# cell_fuses.net
KiCad netlist of a schematic drawn in Altium Designer
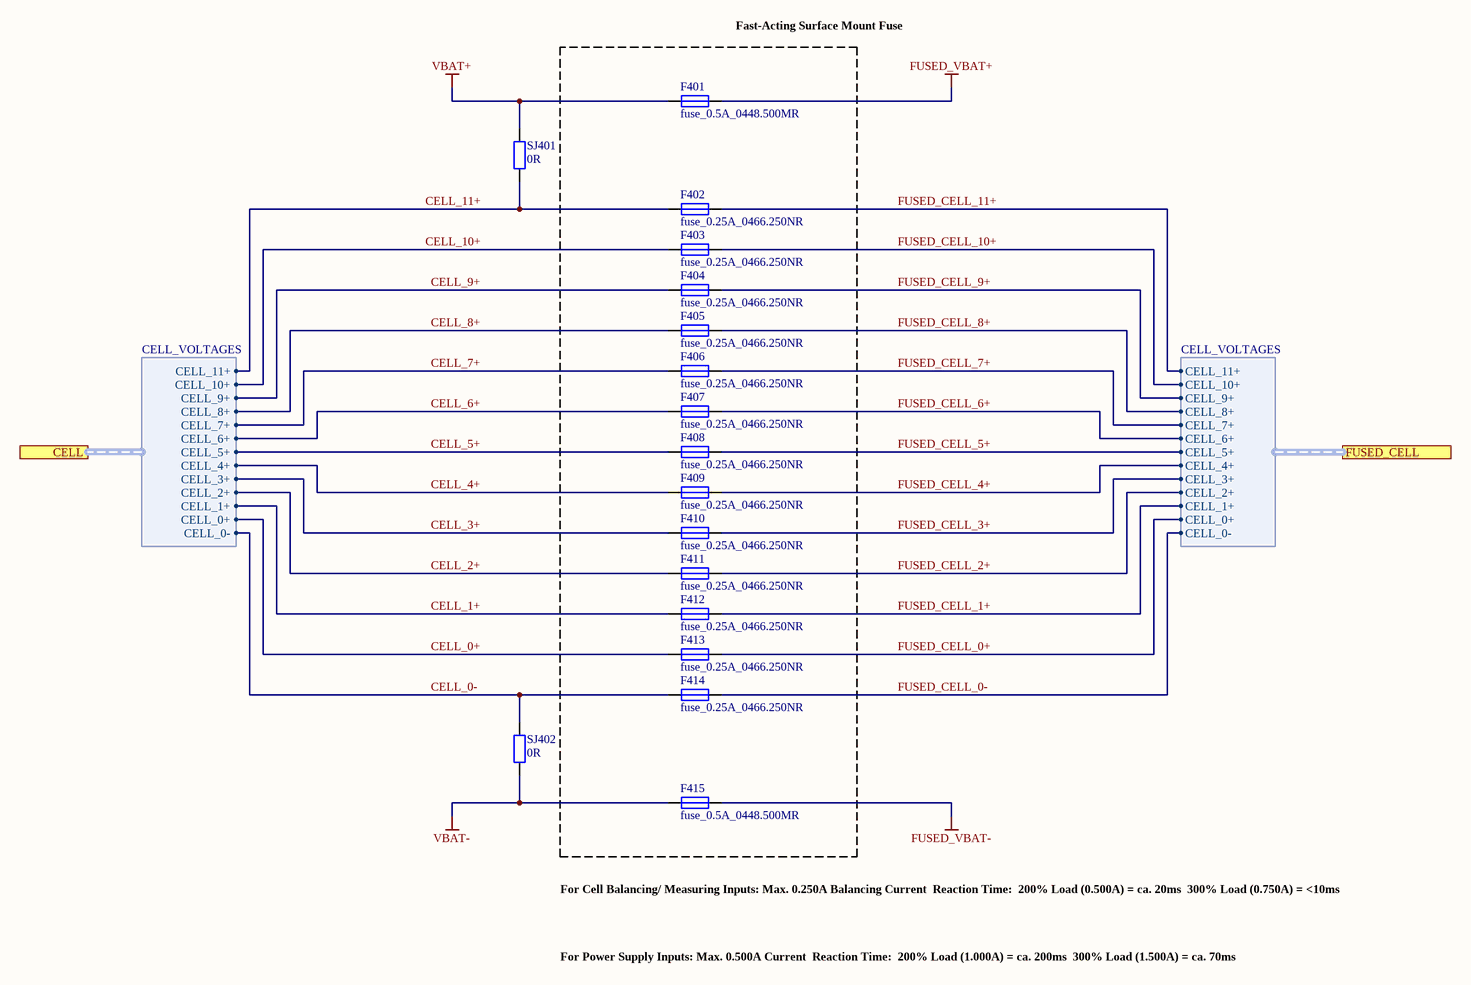
[diagram p0: cell_fuses.SchDoc]

(export (version "E")
  (design (tool "Eeschema 10.0.6"))
  (components
    (comp (ref "F401")
      (value "fuse_0.5A_0448.500MR")
      (footprint "LITTLEFUSE_448")
      (description "Fuse, Surface Mount, NANO2 Series, 500 mA, 125 VAC, 32 VDC, Very Fast Acting, SMD")
      (fields (field (name "MANUFACTURER") "Littlefuse"))
      (libsource (lib "OE750") (part "R_Fuse"))
    )
    (comp (ref "F402")
      (value "fuse_0.25A_0466.250NR")
      (footprint "LITTLEFUSE_466")
      (description "Fuse, Surface Mount, 466 Series, 250 mA, 125 VAC, 125 VDC, Very Fast Acting, 1206")
      (fields (field (name "MANUFACTURER") "Littlefuse"))
      (libsource (lib "OE750") (part "R_Fuse"))
    )
    (comp (ref "F403")
      (value "fuse_0.25A_0466.250NR")
      (footprint "LITTLEFUSE_466")
      (description "Fuse, Surface Mount, 466 Series, 250 mA, 125 VAC, 125 VDC, Very Fast Acting, 1206")
      (fields (field (name "MANUFACTURER") "Littlefuse"))
      (libsource (lib "OE750") (part "R_Fuse"))
    )
    (comp (ref "F404")
      (value "fuse_0.25A_0466.250NR")
      (footprint "LITTLEFUSE_466")
      (description "Fuse, Surface Mount, 466 Series, 250 mA, 125 VAC, 125 VDC, Very Fast Acting, 1206")
      (fields (field (name "MANUFACTURER") "Littlefuse"))
      (libsource (lib "OE750") (part "R_Fuse"))
    )
    (comp (ref "F405")
      (value "fuse_0.25A_0466.250NR")
      (footprint "LITTLEFUSE_466")
      (description "Fuse, Surface Mount, 466 Series, 250 mA, 125 VAC, 125 VDC, Very Fast Acting, 1206")
      (fields (field (name "MANUFACTURER") "Littlefuse"))
      (libsource (lib "OE750") (part "R_Fuse"))
    )
    (comp (ref "F406")
      (value "fuse_0.25A_0466.250NR")
      (footprint "LITTLEFUSE_466")
      (description "Fuse, Surface Mount, 466 Series, 250 mA, 125 VAC, 125 VDC, Very Fast Acting, 1206")
      (fields (field (name "MANUFACTURER") "Littlefuse"))
      (libsource (lib "OE750") (part "R_Fuse"))
    )
    (comp (ref "F407")
      (value "fuse_0.25A_0466.250NR")
      (footprint "LITTLEFUSE_466")
      (description "Fuse, Surface Mount, 466 Series, 250 mA, 125 VAC, 125 VDC, Very Fast Acting, 1206")
      (fields (field (name "MANUFACTURER") "Littlefuse"))
      (libsource (lib "OE750") (part "R_Fuse"))
    )
    (comp (ref "F408")
      (value "fuse_0.25A_0466.250NR")
      (footprint "LITTLEFUSE_466")
      (description "Fuse, Surface Mount, 466 Series, 250 mA, 125 VAC, 125 VDC, Very Fast Acting, 1206")
      (fields (field (name "MANUFACTURER") "Littlefuse"))
      (libsource (lib "OE750") (part "R_Fuse"))
    )
    (comp (ref "F409")
      (value "fuse_0.25A_0466.250NR")
      (footprint "LITTLEFUSE_466")
      (description "Fuse, Surface Mount, 466 Series, 250 mA, 125 VAC, 125 VDC, Very Fast Acting, 1206")
      (fields (field (name "MANUFACTURER") "Littlefuse"))
      (libsource (lib "OE750") (part "R_Fuse"))
    )
    (comp (ref "F410")
      (value "fuse_0.25A_0466.250NR")
      (footprint "LITTLEFUSE_466")
      (description "Fuse, Surface Mount, 466 Series, 250 mA, 125 VAC, 125 VDC, Very Fast Acting, 1206")
      (fields (field (name "MANUFACTURER") "Littlefuse"))
      (libsource (lib "OE750") (part "R_Fuse"))
    )
    (comp (ref "F411")
      (value "fuse_0.25A_0466.250NR")
      (footprint "LITTLEFUSE_466")
      (description "Fuse, Surface Mount, 466 Series, 250 mA, 125 VAC, 125 VDC, Very Fast Acting, 1206")
      (fields (field (name "MANUFACTURER") "Littlefuse"))
      (libsource (lib "OE750") (part "R_Fuse"))
    )
    (comp (ref "F412")
      (value "fuse_0.25A_0466.250NR")
      (footprint "LITTLEFUSE_466")
      (description "Fuse, Surface Mount, 466 Series, 250 mA, 125 VAC, 125 VDC, Very Fast Acting, 1206")
      (fields (field (name "MANUFACTURER") "Littlefuse"))
      (libsource (lib "OE750") (part "R_Fuse"))
    )
    (comp (ref "F413")
      (value "fuse_0.25A_0466.250NR")
      (footprint "LITTLEFUSE_466")
      (description "Fuse, Surface Mount, 466 Series, 250 mA, 125 VAC, 125 VDC, Very Fast Acting, 1206")
      (fields (field (name "MANUFACTURER") "Littlefuse"))
      (libsource (lib "OE750") (part "R_Fuse"))
    )
    (comp (ref "F414")
      (value "fuse_0.25A_0466.250NR")
      (footprint "LITTLEFUSE_466")
      (description "Fuse, Surface Mount, 466 Series, 250 mA, 125 VAC, 125 VDC, Very Fast Acting, 1206")
      (fields (field (name "MANUFACTURER") "Littlefuse"))
      (libsource (lib "OE750") (part "R_Fuse"))
    )
    (comp (ref "F415")
      (value "fuse_0.5A_0448.500MR")
      (footprint "LITTLEFUSE_448")
      (description "Fuse, Surface Mount, NANO2 Series, 500 mA, 125 VAC, 32 VDC, Very Fast Acting, SMD")
      (fields (field (name "MANUFACTURER") "Littlefuse"))
      (libsource (lib "OE750") (part "R_Fuse"))
    )
    (comp (ref "SJ401")
      (value "0R")
      (footprint "RESC1608X05N")
      (description "SMD Resistor 0R 0603")
      (fields (field (name "PART NUMBER") "gen_R_0R_0603") (field (name "POWER") "0.1W"))
      (libsource (lib "OE750") (part "R"))
    )
    (comp (ref "SJ402")
      (value "0R")
      (footprint "RESC1608X05N")
      (description "SMD Resistor 0R 0603")
      (fields (field (name "PART NUMBER") "gen_R_0R_0603") (field (name "POWER") "0.1W"))
      (libsource (lib "OE750") (part "R"))
    )
  )
  (nets
    (net (code "2") (name "/CELL_0+") (class "Default")
      (node (ref "F413") (pin "1") (pinfunction "1_1") (pintype "passive"))
    )
    (net (code "3") (name "/CELL_0-") (class "Default")
      (node (ref "F414") (pin "1") (pinfunction "1_1") (pintype "passive"))
      (node (ref "SJ402") (pin "1") (pinfunction "1_1") (pintype "passive"))
    )
    (net (code "4") (name "/CELL_1+") (class "Default")
      (node (ref "F412") (pin "1") (pinfunction "1_1") (pintype "passive"))
    )
    (net (code "5") (name "/CELL_2+") (class "Default")
      (node (ref "F411") (pin "1") (pinfunction "1_1") (pintype "passive"))
    )
    (net (code "6") (name "/CELL_3+") (class "Default")
      (node (ref "F410") (pin "1") (pinfunction "1_1") (pintype "passive"))
    )
    (net (code "7") (name "/CELL_4+") (class "Default")
      (node (ref "F409") (pin "1") (pinfunction "1_1") (pintype "passive"))
    )
    (net (code "8") (name "/CELL_5+") (class "Default")
      (node (ref "F408") (pin "1") (pinfunction "1_1") (pintype "passive"))
    )
    (net (code "9") (name "/CELL_6+") (class "Default")
      (node (ref "F407") (pin "1") (pinfunction "1_1") (pintype "passive"))
    )
    (net (code "10") (name "/CELL_7+") (class "Default")
      (node (ref "F406") (pin "1") (pinfunction "1_1") (pintype "passive"))
    )
    (net (code "11") (name "/CELL_8+") (class "Default")
      (node (ref "F405") (pin "1") (pinfunction "1_1") (pintype "passive"))
    )
    (net (code "12") (name "/CELL_9+") (class "Default")
      (node (ref "F404") (pin "1") (pinfunction "1_1") (pintype "passive"))
    )
    (net (code "13") (name "/CELL_10+") (class "Default")
      (node (ref "F403") (pin "1") (pinfunction "1_1") (pintype "passive"))
    )
    (net (code "14") (name "/CELL_11+") (class "Default")
      (node (ref "F402") (pin "1") (pinfunction "1_1") (pintype "passive"))
      (node (ref "SJ401") (pin "2") (pinfunction "2_2") (pintype "passive"))
    )
    (net (code "15") (name "/FUSED_CELL_0+") (class "Default")
      (node (ref "F413") (pin "2") (pinfunction "2_2") (pintype "passive"))
    )
    (net (code "16") (name "/FUSED_CELL_0-") (class "Default")
      (node (ref "F414") (pin "2") (pinfunction "2_2") (pintype "passive"))
    )
    (net (code "17") (name "/FUSED_CELL_1+") (class "Default")
      (node (ref "F412") (pin "2") (pinfunction "2_2") (pintype "passive"))
    )
    (net (code "18") (name "/FUSED_CELL_2+") (class "Default")
      (node (ref "F411") (pin "2") (pinfunction "2_2") (pintype "passive"))
    )
    (net (code "19") (name "/FUSED_CELL_3+") (class "Default")
      (node (ref "F410") (pin "2") (pinfunction "2_2") (pintype "passive"))
    )
    (net (code "20") (name "/FUSED_CELL_4+") (class "Default")
      (node (ref "F409") (pin "2") (pinfunction "2_2") (pintype "passive"))
    )
    (net (code "21") (name "/FUSED_CELL_5+") (class "Default")
      (node (ref "F408") (pin "2") (pinfunction "2_2") (pintype "passive"))
    )
    (net (code "22") (name "/FUSED_CELL_6+") (class "Default")
      (node (ref "F407") (pin "2") (pinfunction "2_2") (pintype "passive"))
    )
    (net (code "23") (name "/FUSED_CELL_7+") (class "Default")
      (node (ref "F406") (pin "2") (pinfunction "2_2") (pintype "passive"))
    )
    (net (code "24") (name "/FUSED_CELL_8+") (class "Default")
      (node (ref "F405") (pin "2") (pinfunction "2_2") (pintype "passive"))
    )
    (net (code "25") (name "/FUSED_CELL_9+") (class "Default")
      (node (ref "F404") (pin "2") (pinfunction "2_2") (pintype "passive"))
    )
    (net (code "26") (name "/FUSED_CELL_10+") (class "Default")
      (node (ref "F403") (pin "2") (pinfunction "2_2") (pintype "passive"))
    )
    (net (code "27") (name "/FUSED_CELL_11+") (class "Default")
      (node (ref "F402") (pin "2") (pinfunction "2_2") (pintype "passive"))
    )
    (net (code "29") (name "FUSED_VBAT+") (class "Default")
      (node (ref "F401") (pin "2") (pinfunction "2_2") (pintype "passive"))
    )
    (net (code "30") (name "FUSED_VBAT-") (class "Default")
      (node (ref "F415") (pin "2") (pinfunction "2_2") (pintype "passive"))
    )
    (net (code "31") (name "VBAT+") (class "Default")
      (node (ref "F401") (pin "1") (pinfunction "1_1") (pintype "passive"))
      (node (ref "SJ401") (pin "1") (pinfunction "1_1") (pintype "passive"))
    )
    (net (code "32") (name "VBAT-") (class "Default")
      (node (ref "F415") (pin "1") (pinfunction "1_1") (pintype "passive"))
      (node (ref "SJ402") (pin "2") (pinfunction "2_2") (pintype "passive"))
    )
  )
)
